# CropSenseMovement.net
KiCad netlist of a schematic drawn in Altium Designer
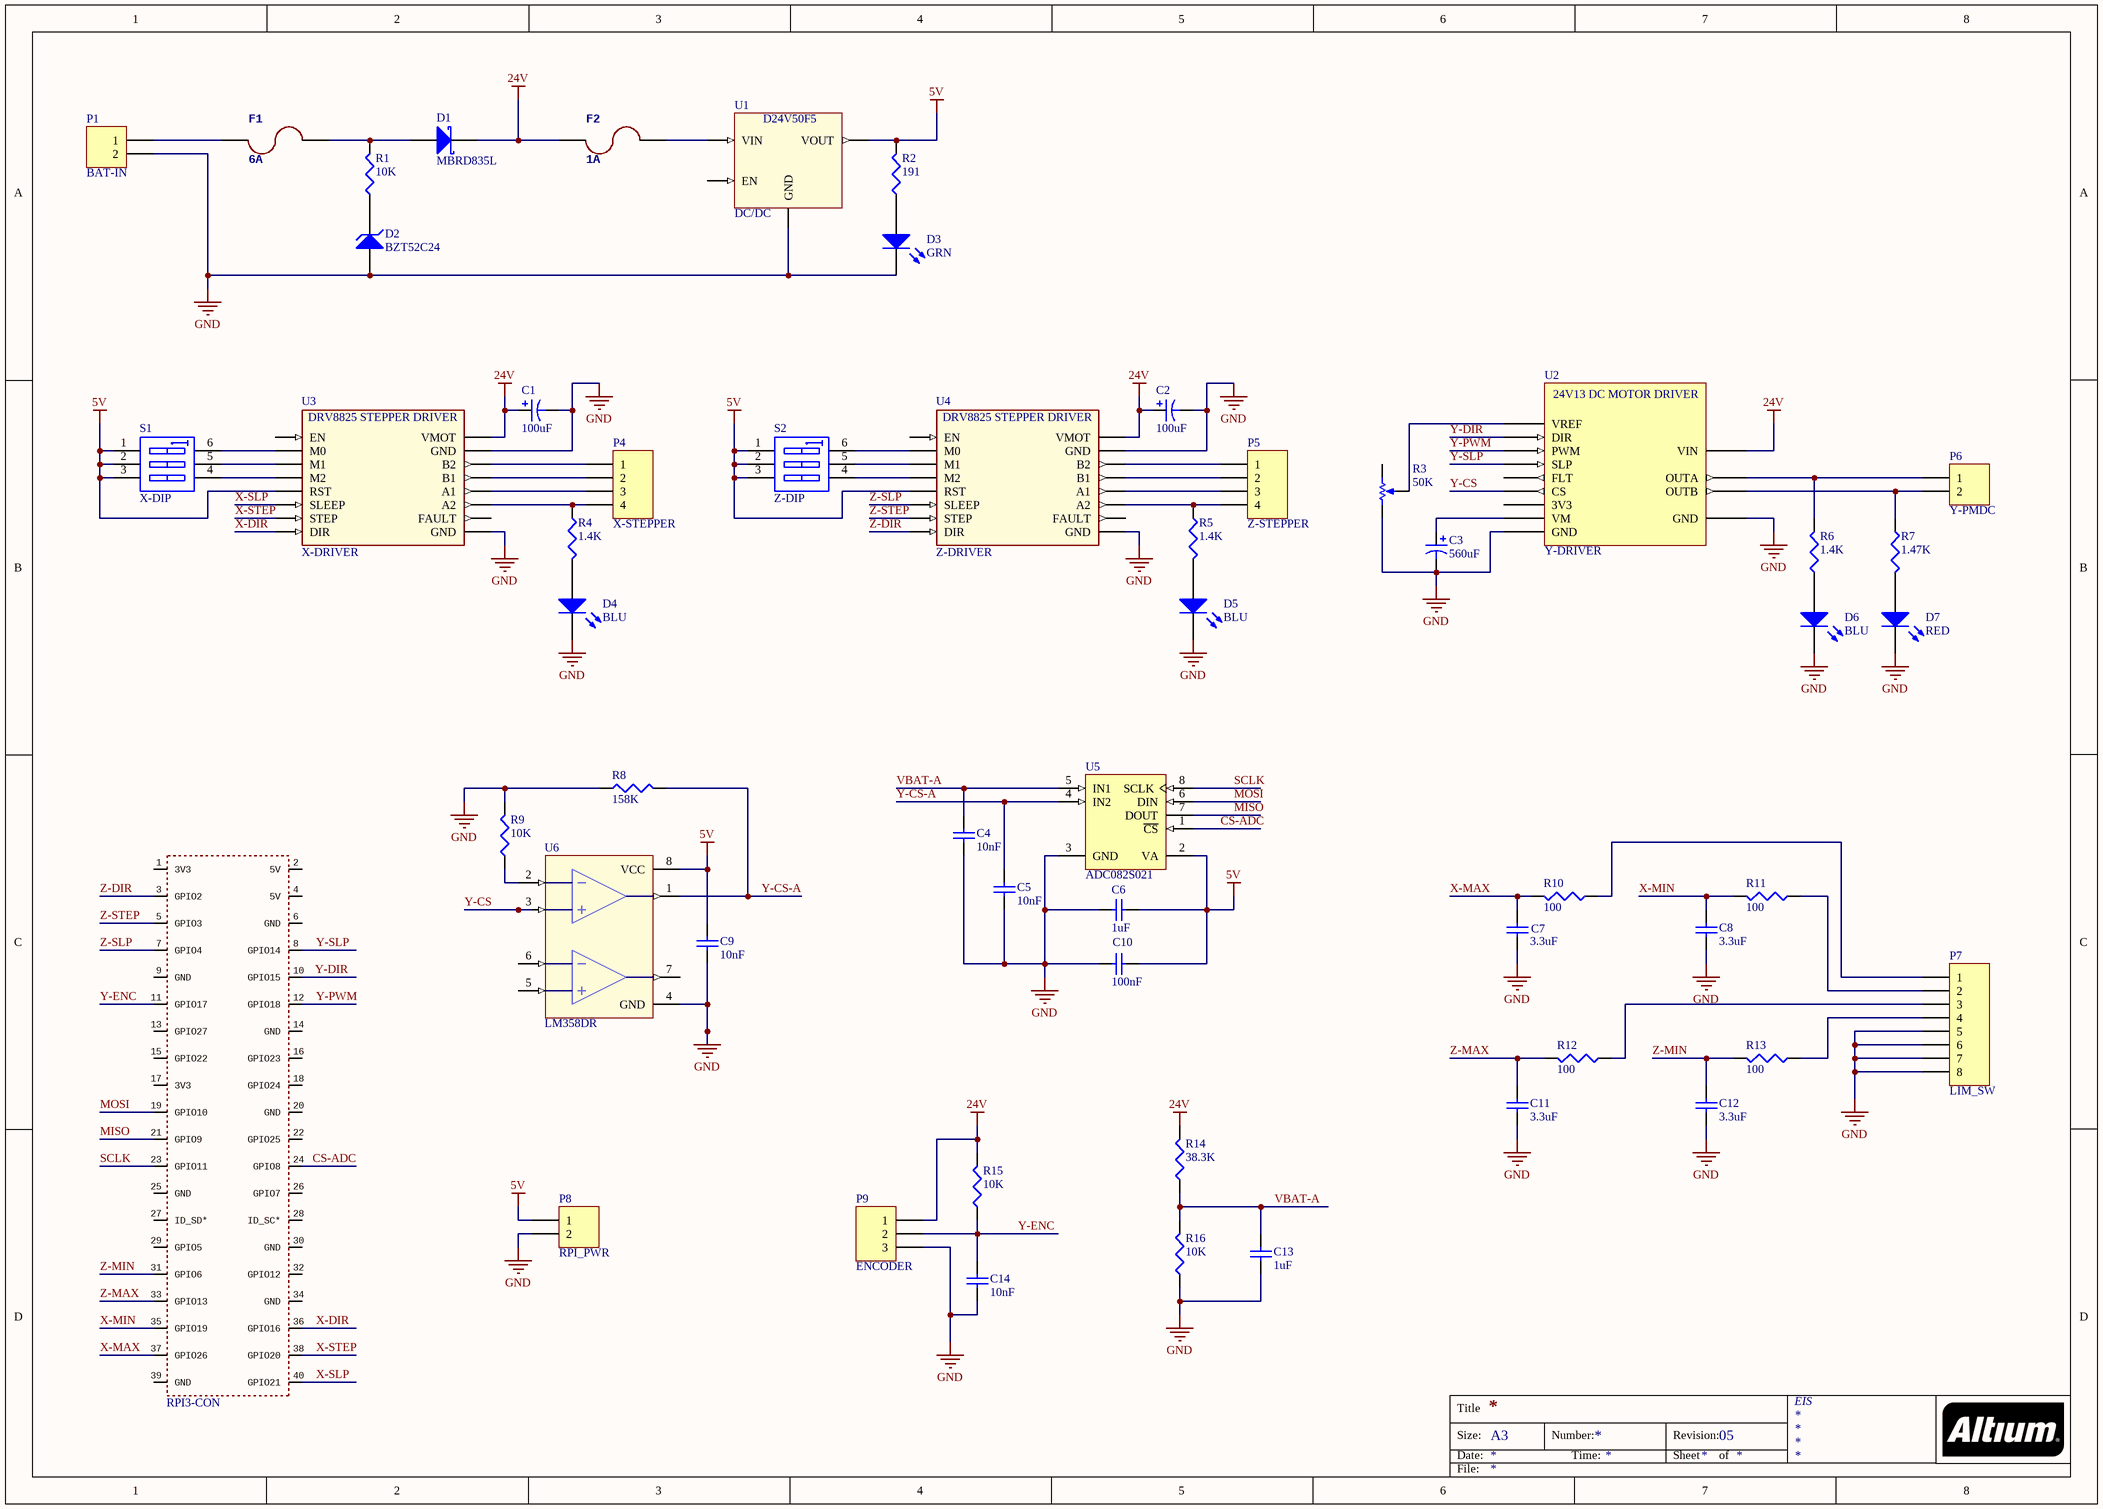
[diagram p0: CropSenseMovement.SchDoc]

(export (version "E")
  (design (tool "Eeschema 10.0.6"))
  (components
    (comp (ref "C1")
      (value "100uF")
      (footprint "CAP 8mm")
      (description "Polarized Capacitor (Axial)")
      (fields (field (name "PUBLISHER") "Altium Limited"))
      (libsource (lib "CropSense_Library") (part "Cap Pol"))
    )
    (comp (ref "C2")
      (value "100uF")
      (footprint "CAP 8mm")
      (description "Polarized Capacitor (Axial)")
      (fields (field (name "PUBLISHER") "Altium Limited"))
      (libsource (lib "CropSense_Library") (part "Cap Pol"))
    )
    (comp (ref "C3")
      (value "560uF")
      (footprint "CAP 12.5MM")
      (description "Polarized Capacitor (Axial)")
      (fields (field (name "PUBLISHER") "Altium Limited"))
      (libsource (lib "CropSense_Library") (part "Cap Pol"))
    )
    (comp (ref "C4")
      (value "10nF")
      (footprint "C1206")
      (description "Capacitor (Semiconductor SIM Model)")
      (fields (field (name "PUBLISHER") "Altium Limited"))
      (libsource (lib "Miscellaneous Devices") (part "Cap Semi"))
    )
    (comp (ref "C5")
      (value "10nF")
      (footprint "C1206")
      (description "Capacitor (Semiconductor SIM Model)")
      (fields (field (name "PUBLISHER") "Altium Limited"))
      (libsource (lib "Miscellaneous Devices") (part "Cap Semi"))
    )
    (comp (ref "C6")
      (value "1uF")
      (footprint "C1206")
      (description "Capacitor (Semiconductor SIM Model)")
      (fields (field (name "PUBLISHER") "Altium Limited"))
      (libsource (lib "Miscellaneous Devices") (part "Cap Semi"))
    )
    (comp (ref "C7")
      (value "3.3uF")
      (footprint "C1206")
      (description "Capacitor (Semiconductor SIM Model)")
      (fields (field (name "PUBLISHER") "Altium Limited"))
      (libsource (lib "Miscellaneous Devices") (part "Cap Semi"))
    )
    (comp (ref "C8")
      (value "3.3uF")
      (footprint "C1206")
      (description "Capacitor (Semiconductor SIM Model)")
      (fields (field (name "PUBLISHER") "Altium Limited"))
      (libsource (lib "Miscellaneous Devices") (part "Cap Semi"))
    )
    (comp (ref "C9")
      (value "10nF")
      (footprint "C1206")
      (description "Capacitor (Semiconductor SIM Model)")
      (fields (field (name "PUBLISHER") "Altium Limited"))
      (libsource (lib "Miscellaneous Devices") (part "Cap Semi"))
    )
    (comp (ref "C10")
      (value "100nF")
      (footprint "C1206")
      (description "Capacitor (Semiconductor SIM Model)")
      (fields (field (name "PUBLISHER") "Altium Limited"))
      (libsource (lib "Miscellaneous Devices") (part "Cap Semi"))
    )
    (comp (ref "C11")
      (value "3.3uF")
      (footprint "C1206")
      (description "Capacitor (Semiconductor SIM Model)")
      (fields (field (name "PUBLISHER") "Altium Limited"))
      (libsource (lib "Miscellaneous Devices") (part "Cap Semi"))
    )
    (comp (ref "C12")
      (value "3.3uF")
      (footprint "C1206")
      (description "Capacitor (Semiconductor SIM Model)")
      (fields (field (name "PUBLISHER") "Altium Limited"))
      (libsource (lib "Miscellaneous Devices") (part "Cap Semi"))
    )
    (comp (ref "C13")
      (value "1uF")
      (footprint "C1206")
      (description "Capacitor (Semiconductor SIM Model)")
      (fields (field (name "PUBLISHER") "Altium Limited"))
      (libsource (lib "Miscellaneous Devices") (part "Cap Semi"))
    )
    (comp (ref "C14")
      (value "10nF")
      (footprint "C1206")
      (description "Capacitor (Semiconductor SIM Model)")
      (fields (field (name "PUBLISHER") "Altium Limited"))
      (libsource (lib "Miscellaneous Devices") (part "Cap Semi"))
    )
    (comp (ref "D1")
      (value "MBRD835L")
      (footprint "DPAK229P991X238-3N")
      (description "Schottky Diode")
      (fields (field (name "PUBLISHER") "Altium Limited"))
      (libsource (lib "CropSense_Library") (part "D Schottky"))
    )
    (comp (ref "D2")
      (value "BZT52C24")
      (footprint "SOD123")
      (description "Zener Diode")
      (fields (field (name "PUBLISHER") "Altium Limited"))
      (libsource (lib "CropSense_Library") (part "D Zener"))
    )
    (comp (ref "D3")
      (value "GRN")
      (footprint "1206 SMD LED")
      (description "Typical INFRARED GaAs LED")
      (fields (field (name "PUBLISHER") "Altium Limited"))
      (libsource (lib "CropSense_Library") (part "LED"))
    )
    (comp (ref "D4")
      (value "BLU")
      (footprint "1206 SMD LED")
      (description "Typical INFRARED GaAs LED")
      (fields (field (name "PUBLISHER") "Altium Limited"))
      (libsource (lib "CropSense_Library") (part "LED"))
    )
    (comp (ref "D5")
      (value "BLU")
      (footprint "1206 SMD LED")
      (description "Typical INFRARED GaAs LED")
      (fields (field (name "PUBLISHER") "Altium Limited"))
      (libsource (lib "CropSense_Library") (part "LED"))
    )
    (comp (ref "D6")
      (value "BLU")
      (footprint "1206 SMD LED")
      (description "Typical INFRARED GaAs LED")
      (fields (field (name "PUBLISHER") "Altium Limited"))
      (libsource (lib "CropSense_Library") (part "LED"))
    )
    (comp (ref "D7")
      (value "RED")
      (footprint "1206 SMD LED")
      (description "Typical INFRARED GaAs LED")
      (fields (field (name "PUBLISHER") "Altium Limited"))
      (libsource (lib "CropSense_Library") (part "LED"))
    )
    (comp (ref "F1")
      (value "6A")
      (footprint "5X20MM_LITTLEFUSE_CARTRIDGE")
      (description "5mm x 20mm Littlefuse Cartridge")
      (libsource (lib "CropSense_Library") (part "FUSE_5X20_LITTLEFUSE"))
    )
    (comp (ref "F2")
      (value "1A")
      (footprint "5X20MM_LITTLEFUSE_CARTRIDGE")
      (description "5mm x 20mm Littlefuse Cartridge")
      (libsource (lib "CropSense_Library") (part "FUSE_5X20_LITTLEFUSE"))
    )
    (comp (ref "P1")
      (value "BAT-IN")
      (footprint "MOLEX_MINI_1X2CCT")
      (description "Molex Mini Fit 2 cct Double Row")
      (libsource (lib "") (part "MOLEX_MINI_1X2_1"))
    )
    (comp (ref "P4")
      (value "X-STEPPER")
      (footprint "MOLEX_Micro_4x1CCT")
      (description "MOLEX_MICRO_4x1")
      (libsource (lib "CropSense_Library") (part "MOLEX_MICRO_4x1"))
    )
    (comp (ref "P5")
      (value "Z-STEPPER")
      (footprint "MOLEX_Micro_4x1CCT")
      (description "MOLEX_MICRO_4x1")
      (libsource (lib "CropSense_Library") (part "MOLEX_MICRO_4x1"))
    )
    (comp (ref "P6")
      (value "Y-PMDC")
      (footprint "MOLEX_MINI_1X2CCT")
      (description "Molex Mini Fit 2 cct Double Row")
      (libsource (lib "CropSense_Library") (part "MOLEX_MINI_1X2"))
    )
    (comp (ref "P7")
      (value "LIM_SW")
      (footprint "MOLEX_MICRO_4X2CCT")
      (description "Molex Micro Fit 8 cct Double Row")
      (libsource (lib "CropSense_Library") (part "MOLEX_MICRO_4X2"))
    )
    (comp (ref "P8")
      (value "RPI_PWR")
      (footprint "MOLEX_MICRO_2X1CCT")
      (description "Molex Micro Fit 2 cct Single Row")
      (libsource (lib "CropSense_Library") (part "MOLEX_MICRO_2x1"))
    )
    (comp (ref "P9")
      (value "ENCODER")
      (footprint "MOLEX_MICRO_3X1CCT")
      (description "Molex Micro Fit 3 cct Single Row")
      (libsource (lib "CropSense_Library") (part "MOLEX_MICRO_3x1"))
    )
    (comp (ref "R1")
      (value "10K")
      (footprint "6-0805_N")
      (description "Resistor")
      (fields (field (name "PUBLISHER") "Altium Limited"))
      (libsource (lib "Miscellaneous Devices") (part "Res3"))
    )
    (comp (ref "R2")
      (value "191")
      (footprint "6-0805_N")
      (description "Resistor")
      (fields (field (name "PUBLISHER") "Altium Limited"))
      (libsource (lib "Miscellaneous Devices") (part "Res3"))
    )
    (comp (ref "R3")
      (value "50K")
      (footprint "Trimpot TC33")
      (description "TRIMMER 50K OHM 0.1W SMD")
      (fields (field (name "PUBLISHER") "Altium Limited"))
      (libsource (lib "CropSense_Library") (part "RPot"))
    )
    (comp (ref "R4")
      (value "1.4K")
      (footprint "6-0805_N")
      (description "Resistor")
      (fields (field (name "PUBLISHER") "Altium Limited"))
      (libsource (lib "Miscellaneous Devices") (part "Res3"))
    )
    (comp (ref "R5")
      (value "1.4K")
      (footprint "6-0805_N")
      (description "Resistor")
      (fields (field (name "PUBLISHER") "Altium Limited"))
      (libsource (lib "Miscellaneous Devices") (part "Res3"))
    )
    (comp (ref "R6")
      (value "1.4K")
      (footprint "6-0805_N")
      (description "Resistor")
      (fields (field (name "PUBLISHER") "Altium Limited"))
      (libsource (lib "Miscellaneous Devices") (part "Res3"))
    )
    (comp (ref "R7")
      (value "1.47K")
      (footprint "6-0805_N")
      (description "Resistor")
      (fields (field (name "PUBLISHER") "Altium Limited"))
      (libsource (lib "Miscellaneous Devices") (part "Res3"))
    )
    (comp (ref "R8")
      (value "158K")
      (footprint "6-0805_N")
      (description "Resistor")
      (fields (field (name "PUBLISHER") "Altium Limited"))
      (libsource (lib "Miscellaneous Devices") (part "Res3"))
    )
    (comp (ref "R9")
      (value "10K")
      (footprint "6-0805_N")
      (description "Resistor")
      (fields (field (name "PUBLISHER") "Altium Limited"))
      (libsource (lib "Miscellaneous Devices") (part "Res3"))
    )
    (comp (ref "R10")
      (value "100")
      (footprint "6-0805_N")
      (description "Resistor")
      (fields (field (name "PUBLISHER") "Altium Limited"))
      (libsource (lib "Miscellaneous Devices") (part "Res3"))
    )
    (comp (ref "R11")
      (value "100")
      (footprint "6-0805_N")
      (description "Resistor")
      (fields (field (name "PUBLISHER") "Altium Limited"))
      (libsource (lib "Miscellaneous Devices") (part "Res3"))
    )
    (comp (ref "R12")
      (value "100")
      (footprint "6-0805_N")
      (description "Resistor")
      (fields (field (name "PUBLISHER") "Altium Limited"))
      (libsource (lib "Miscellaneous Devices") (part "Res3"))
    )
    (comp (ref "R13")
      (value "100")
      (footprint "6-0805_N")
      (description "Resistor")
      (fields (field (name "PUBLISHER") "Altium Limited"))
      (libsource (lib "Miscellaneous Devices") (part "Res3"))
    )
    (comp (ref "R14")
      (value "38.3K")
      (footprint "6-0805_N")
      (description "Resistor")
      (fields (field (name "PUBLISHER") "Altium Limited"))
      (libsource (lib "Miscellaneous Devices") (part "Res3"))
    )
    (comp (ref "R15")
      (value "10K")
      (footprint "6-0805_N")
      (description "Resistor")
      (fields (field (name "PUBLISHER") "Altium Limited"))
      (libsource (lib "Miscellaneous Devices") (part "Res3"))
    )
    (comp (ref "R16")
      (value "10K")
      (footprint "6-0805_N")
      (description "Resistor")
      (fields (field (name "PUBLISHER") "Altium Limited"))
      (libsource (lib "Miscellaneous Devices") (part "Res3"))
    )
    (comp (ref "S1")
      (value "X-DIP")
      (footprint "DIP-6")
      (description "DIP Switch, 3 Position, SPST")
      (fields (field (name "PUBLISHER") "Altium Limited"))
      (libsource (lib "Miscellaneous Devices") (part "SW DIP-3"))
    )
    (comp (ref "S2")
      (value "Z-DIP")
      (footprint "DIP-6")
      (description "DIP Switch, 3 Position, SPST")
      (fields (field (name "PUBLISHER") "Altium Limited"))
      (libsource (lib "Miscellaneous Devices") (part "SW DIP-3"))
    )
    (comp (ref "U$2")
      (value "RPI3-CON")
      (footprint "CONNECTOR")
      (libsource (lib "e14_Rpi3_RevA") (part "RPI3_CON"))
    )
    (comp (ref "U1")
      (value "DC/DC")
      (footprint "D24VXXFX_BREAKOUT")
      (libsource (lib "CropSense_Library") (part "D24V50F5"))
    )
    (comp (ref "U2")
      (value "Y-DRIVER")
      (footprint "24V13_BREAKOUT")
      (libsource (lib "CropSense_Library") (part "24V13_BREAKOUT"))
    )
    (comp (ref "U3")
      (value "X-DRIVER")
      (footprint "DRV8825_BREAKOUT")
      (libsource (lib "CropSense_Library") (part "DRV8825_BREAKOUT"))
    )
    (comp (ref "U4")
      (value "Z-DRIVER")
      (footprint "DRV8825_BREAKOUT")
      (libsource (lib "CropSense_Library") (part "DRV8825_BREAKOUT"))
    )
    (comp (ref "U5")
      (value "ADC082S021")
      (footprint "TI-DGK8_N")
      (description "2 Channel, 50 to 200 kSPS 8-Bit ADC, -40 to 85 degC, 8-pin SOP (DGK8), Green (RoHS & no Sb/Br)")
      (fields
        (field (name "PARTNUMBER") "ADC122S051QIMM/NOPB")
        (field (name "MANUFACTURER") "Texas Instruments")
      )
      (libsource (lib "Altium Content Vault") (part "CMP-0003-00004-1"))
    )
    (comp (ref "U6")
      (value "LM358DR")
      (footprint "SOIC127P600X175-8N")
      (libsource (lib "CropSense_Library") (part "LM358DR"))
    )
  )
  (nets
    (net (code "1") (name "/CS-ADC") (class "Default")
      (node (ref "U$2") (pin "24") (pinfunction "GPIO8_24") (pintype "passive"))
      (node (ref "U5") (pin "1") (pinfunction "~{CS}_1") (pintype "input"))
    )
    (net (code "2") (name "/MISO") (class "Default")
      (node (ref "U$2") (pin "21") (pinfunction "GPIO9_21") (pintype "passive"))
      (node (ref "U5") (pin "7") (pinfunction "DOUT_7") (pintype "tri_state"))
    )
    (net (code "3") (name "/MOSI") (class "Default")
      (node (ref "U$2") (pin "19") (pinfunction "GPIO10_19") (pintype "passive"))
      (node (ref "U5") (pin "6") (pinfunction "DIN_6") (pintype "input"))
    )
    (net (code "4") (name "/SCLK") (class "Default")
      (node (ref "U$2") (pin "23") (pinfunction "GPIO11_23") (pintype "passive"))
      (node (ref "U5") (pin "8") (pinfunction "SCLK_8") (pintype "input"))
    )
    (net (code "5") (name "/VBAT-A") (class "Default")
      (node (ref "C13") (pin "2") (pinfunction "2_2") (pintype "passive"))
      (node (ref "C4") (pin "1") (pinfunction "1_1") (pintype "passive"))
      (node (ref "R14") (pin "1") (pinfunction "1_1") (pintype "passive"))
      (node (ref "R16") (pin "2") (pinfunction "2_2") (pintype "passive"))
      (node (ref "U5") (pin "5") (pinfunction "IN1_5") (pintype "input"))
    )
    (net (code "6") (name "/X-DIR") (class "Default")
      (node (ref "U$2") (pin "36") (pinfunction "GPIO16_36") (pintype "passive"))
      (node (ref "U3") (pin "DIR") (pinfunction "DIR_DIR") (pintype "input"))
    )
    (net (code "7") (name "/X-MAX") (class "Default")
      (node (ref "C7") (pin "2") (pinfunction "2_2") (pintype "passive"))
      (node (ref "R10") (pin "2") (pinfunction "2_2") (pintype "passive"))
      (node (ref "U$2") (pin "37") (pinfunction "GPIO26_37") (pintype "passive"))
    )
    (net (code "8") (name "/X-MIN") (class "Default")
      (node (ref "C8") (pin "2") (pinfunction "2_2") (pintype "passive"))
      (node (ref "R11") (pin "2") (pinfunction "2_2") (pintype "passive"))
      (node (ref "U$2") (pin "35") (pinfunction "GPIO19_35") (pintype "passive"))
    )
    (net (code "9") (name "/X-SLP") (class "Default")
      (node (ref "U$2") (pin "40") (pinfunction "GPIO21_40") (pintype "passive"))
      (node (ref "U3") (pin "SLP") (pinfunction "SLEEP_SLP") (pintype "input"))
    )
    (net (code "10") (name "/X-STEP") (class "Default")
      (node (ref "U$2") (pin "38") (pinfunction "GPIO20_38") (pintype "passive"))
      (node (ref "U3") (pin "STEP") (pinfunction "STEP_STEP") (pintype "input"))
    )
    (net (code "11") (name "/Y-CS") (class "Default")
      (node (ref "U2") (pin "CS") (pinfunction "CS_CS") (pintype "output"))
      (node (ref "U6") (pin "3") (pinfunction "IN1+_3") (pintype "input"))
    )
    (net (code "12") (name "/Y-CS-A") (class "Default")
      (node (ref "C5") (pin "1") (pinfunction "1_1") (pintype "passive"))
      (node (ref "R8") (pin "2") (pinfunction "2_2") (pintype "passive"))
      (node (ref "U5") (pin "4") (pinfunction "IN2_4") (pintype "input"))
      (node (ref "U6") (pin "1") (pinfunction "OUT1_1") (pintype "output"))
    )
    (net (code "13") (name "/Y-DIR") (class "Default")
      (node (ref "U$2") (pin "10") (pinfunction "GPIO15_10") (pintype "passive"))
      (node (ref "U2") (pin "DIR") (pinfunction "DIR_DIR") (pintype "input"))
    )
    (net (code "14") (name "/Y-ENC") (class "Default")
      (node (ref "C14") (pin "2") (pinfunction "2_2") (pintype "passive"))
      (node (ref "P9") (pin "2") (pinfunction "2_2") (pintype "passive"))
      (node (ref "R15") (pin "1") (pinfunction "1_1") (pintype "passive"))
      (node (ref "U$2") (pin "11") (pinfunction "GPIO17_11") (pintype "passive"))
    )
    (net (code "15") (name "/Y-PWM") (class "Default")
      (node (ref "U$2") (pin "12") (pinfunction "GPIO18_12") (pintype "passive"))
      (node (ref "U2") (pin "PWM") (pinfunction "PWM_PWM") (pintype "input"))
    )
    (net (code "16") (name "/Y-SLP") (class "Default")
      (node (ref "U$2") (pin "8") (pinfunction "GPIO14_8") (pintype "passive"))
      (node (ref "U2") (pin "SLP") (pinfunction "SLP_SLP") (pintype "input"))
    )
    (net (code "17") (name "/Z-DIR") (class "Default")
      (node (ref "U$2") (pin "3") (pinfunction "GPIO2_3") (pintype "passive"))
      (node (ref "U4") (pin "DIR") (pinfunction "DIR_DIR") (pintype "input"))
    )
    (net (code "18") (name "/Z-MAX") (class "Default")
      (node (ref "C11") (pin "2") (pinfunction "2_2") (pintype "passive"))
      (node (ref "R12") (pin "2") (pinfunction "2_2") (pintype "passive"))
      (node (ref "U$2") (pin "33") (pinfunction "GPIO13_33") (pintype "passive"))
    )
    (net (code "19") (name "/Z-MIN") (class "Default")
      (node (ref "C12") (pin "2") (pinfunction "2_2") (pintype "passive"))
      (node (ref "R13") (pin "2") (pinfunction "2_2") (pintype "passive"))
      (node (ref "U$2") (pin "31") (pinfunction "GPIO6_31") (pintype "passive"))
    )
    (net (code "20") (name "/Z-SLP") (class "Default")
      (node (ref "U$2") (pin "7") (pinfunction "GPIO4_7") (pintype "passive"))
      (node (ref "U4") (pin "SLP") (pinfunction "SLEEP_SLP") (pintype "input"))
    )
    (net (code "21") (name "/Z-STEP") (class "Default")
      (node (ref "U$2") (pin "5") (pinfunction "GPIO3_5") (pintype "passive"))
      (node (ref "U4") (pin "STEP") (pinfunction "STEP_STEP") (pintype "input"))
    )
    (net (code "22") (name "5V") (class "Default")
      (node (ref "C10") (pin "2") (pinfunction "2_2") (pintype "passive"))
      (node (ref "C6") (pin "2") (pinfunction "2_2") (pintype "passive"))
      (node (ref "C9") (pin "1") (pinfunction "1_1") (pintype "passive"))
      (node (ref "P8") (pin "1") (pinfunction "1_1") (pintype "passive"))
      (node (ref "R2") (pin "2") (pinfunction "2_2") (pintype "passive"))
      (node (ref "S1") (pin "1") (pinfunction "A1_1") (pintype "passive"))
      (node (ref "S1") (pin "2") (pinfunction "A2_2") (pintype "passive"))
      (node (ref "S1") (pin "3") (pinfunction "A3_3") (pintype "passive"))
      (node (ref "S2") (pin "1") (pinfunction "A1_1") (pintype "passive"))
      (node (ref "S2") (pin "2") (pinfunction "A2_2") (pintype "passive"))
      (node (ref "S2") (pin "3") (pinfunction "A3_3") (pintype "passive"))
      (node (ref "U1") (pin "VOUT") (pinfunction "VOUT_VOUT") (pintype "output"))
      (node (ref "U3") (pin "RST") (pinfunction "RST_RST") (pintype "passive"))
      (node (ref "U4") (pin "RST") (pinfunction "RST_RST") (pintype "passive"))
      (node (ref "U5") (pin "2") (pinfunction "VA_2") (pintype "power_in"))
      (node (ref "U6") (pin "8") (pinfunction "VCC_8") (pintype "power_in"))
    )
    (net (code "23") (name "24V") (class "Default")
      (node (ref "C1") (pin "1") (pinfunction "1_1") (pintype "passive"))
      (node (ref "C2") (pin "1") (pinfunction "1_1") (pintype "passive"))
      (node (ref "D1") (pin "2") (pinfunction "K_2") (pintype "passive"))
      (node (ref "F2") (pin "1") (pinfunction "1_1") (pintype "passive"))
      (node (ref "P9") (pin "1") (pinfunction "1_1") (pintype "passive"))
      (node (ref "R14") (pin "2") (pinfunction "2_2") (pintype "passive"))
      (node (ref "R15") (pin "2") (pinfunction "2_2") (pintype "passive"))
      (node (ref "U2") (pin "VIN") (pinfunction "VIN_VIN") (pintype "power_in"))
      (node (ref "U3") (pin "VMOT") (pinfunction "VMOT_VMOT") (pintype "power_in"))
      (node (ref "U4") (pin "VMOT") (pinfunction "VMOT_VMOT") (pintype "power_in"))
    )
    (net (code "24") (name "GND") (class "Default")
      (node (ref "C1") (pin "2") (pinfunction "2_2") (pintype "passive"))
      (node (ref "C10") (pin "1") (pinfunction "1_1") (pintype "passive"))
      (node (ref "C11") (pin "1") (pinfunction "1_1") (pintype "passive"))
      (node (ref "C12") (pin "1") (pinfunction "1_1") (pintype "passive"))
      (node (ref "C13") (pin "1") (pinfunction "1_1") (pintype "passive"))
      (node (ref "C14") (pin "1") (pinfunction "1_1") (pintype "passive"))
      (node (ref "C2") (pin "2") (pinfunction "2_2") (pintype "passive"))
      (node (ref "C3") (pin "2") (pinfunction "2_2") (pintype "passive"))
      (node (ref "C4") (pin "2") (pinfunction "2_2") (pintype "passive"))
      (node (ref "C5") (pin "2") (pinfunction "2_2") (pintype "passive"))
      (node (ref "C6") (pin "1") (pinfunction "1_1") (pintype "passive"))
      (node (ref "C7") (pin "1") (pinfunction "1_1") (pintype "passive"))
      (node (ref "C8") (pin "1") (pinfunction "1_1") (pintype "passive"))
      (node (ref "C9") (pin "2") (pinfunction "2_2") (pintype "passive"))
      (node (ref "D2") (pin "1") (pinfunction "A_1") (pintype "passive"))
      (node (ref "D3") (pin "2") (pinfunction "K_2") (pintype "passive"))
      (node (ref "D4") (pin "2") (pinfunction "K_2") (pintype "passive"))
      (node (ref "D5") (pin "2") (pinfunction "K_2") (pintype "passive"))
      (node (ref "D6") (pin "2") (pinfunction "K_2") (pintype "passive"))
      (node (ref "D7") (pin "2") (pinfunction "K_2") (pintype "passive"))
      (node (ref "P1") (pin "2") (pinfunction "2_2") (pintype "passive"))
      (node (ref "P7") (pin "5") (pinfunction "5_5") (pintype "passive"))
      (node (ref "P7") (pin "6") (pinfunction "6_6") (pintype "passive"))
      (node (ref "P7") (pin "7") (pinfunction "7_7") (pintype "passive"))
      (node (ref "P7") (pin "8") (pinfunction "8_8") (pintype "passive"))
      (node (ref "P8") (pin "2") (pinfunction "2_2") (pintype "passive"))
      (node (ref "P9") (pin "3") (pinfunction "3_3") (pintype "passive"))
      (node (ref "R16") (pin "1") (pinfunction "1_1") (pintype "passive"))
      (node (ref "R3") (pin "3") (pinfunction "TOP_3") (pintype "passive"))
      (node (ref "R8") (pin "1") (pinfunction "1_1") (pintype "passive"))
      (node (ref "R9") (pin "2") (pinfunction "2_2") (pintype "passive"))
      (node (ref "U1") (pin "GND") (pinfunction "GND_GND") (pintype "passive"))
      (node (ref "U2") (pin "GND") (pinfunction "GND_GND") (pintype "passive"))
      (node (ref "U3") (pin "GND") (pinfunction "GND_GND") (pintype "power_in"))
      (node (ref "U4") (pin "GND") (pinfunction "GND_GND") (pintype "power_in"))
      (node (ref "U5") (pin "3") (pinfunction "GND_3") (pintype "power_in"))
      (node (ref "U6") (pin "4") (pinfunction "GND_4") (pintype "power_in"))
    )
    (net (code "25") (name "Net-(C3-Pad1)") (class "Default")
      (node (ref "C3") (pin "1") (pinfunction "1_1") (pintype "passive"))
      (node (ref "U2") (pin "VM") (pinfunction "VM_VM") (pintype "passive"))
    )
    (net (code "26") (name "Net-(D1-A)") (class "Default")
      (node (ref "D1") (pin "1") (pinfunction "A_1") (pintype "passive"))
      (node (ref "F1") (pin "2") (pinfunction "2_2") (pintype "passive"))
      (node (ref "R1") (pin "2") (pinfunction "2_2") (pintype "passive"))
    )
    (net (code "27") (name "Net-(D2-K)") (class "Default")
      (node (ref "D2") (pin "2") (pinfunction "K_2") (pintype "passive"))
      (node (ref "R1") (pin "1") (pinfunction "1_1") (pintype "passive"))
    )
    (net (code "28") (name "Net-(D3-A)") (class "Default")
      (node (ref "D3") (pin "1") (pinfunction "A_1") (pintype "passive"))
      (node (ref "R2") (pin "1") (pinfunction "1_1") (pintype "passive"))
    )
    (net (code "29") (name "Net-(D4-A)") (class "Default")
      (node (ref "D4") (pin "1") (pinfunction "A_1") (pintype "passive"))
      (node (ref "R4") (pin "2") (pinfunction "2_2") (pintype "passive"))
    )
    (net (code "30") (name "Net-(D5-A)") (class "Default")
      (node (ref "D5") (pin "1") (pinfunction "A_1") (pintype "passive"))
      (node (ref "R5") (pin "2") (pinfunction "2_2") (pintype "passive"))
    )
    (net (code "31") (name "Net-(D6-A)") (class "Default")
      (node (ref "D6") (pin "1") (pinfunction "A_1") (pintype "passive"))
      (node (ref "R6") (pin "1") (pinfunction "1_1") (pintype "passive"))
    )
    (net (code "32") (name "Net-(D7-A)") (class "Default")
      (node (ref "D7") (pin "1") (pinfunction "A_1") (pintype "passive"))
      (node (ref "R7") (pin "2") (pinfunction "2_2") (pintype "passive"))
    )
    (net (code "33") (name "Net-(F1-Pad1)") (class "Default")
      (node (ref "F1") (pin "1") (pinfunction "1_1") (pintype "passive"))
      (node (ref "P1") (pin "1") (pinfunction "1_1") (pintype "passive"))
    )
    (net (code "34") (name "Net-(F2-Pad2)") (class "Default")
      (node (ref "F2") (pin "2") (pinfunction "2_2") (pintype "passive"))
      (node (ref "U1") (pin "VIN") (pinfunction "VIN_VIN") (pintype "input"))
    )
    (net (code "35") (name "Net-(P4-Pad1)") (class "Default")
      (node (ref "P4") (pin "1") (pinfunction "1_1") (pintype "passive"))
      (node (ref "U3") (pin "B2") (pinfunction "B2_B2") (pintype "output"))
    )
    (net (code "36") (name "Net-(P4-Pad2)") (class "Default")
      (node (ref "P4") (pin "2") (pinfunction "2_2") (pintype "passive"))
      (node (ref "U3") (pin "B1") (pinfunction "B1_B1") (pintype "output"))
    )
    (net (code "37") (name "Net-(P4-Pad3)") (class "Default")
      (node (ref "P4") (pin "3") (pinfunction "3_3") (pintype "passive"))
      (node (ref "U3") (pin "A1") (pinfunction "A1_A1") (pintype "output"))
    )
    (net (code "38") (name "Net-(P4-Pad4)") (class "Default")
      (node (ref "P4") (pin "4") (pinfunction "4_4") (pintype "passive"))
      (node (ref "R4") (pin "1") (pinfunction "1_1") (pintype "passive"))
      (node (ref "U3") (pin "A2") (pinfunction "A2_A2") (pintype "output"))
    )
    (net (code "39") (name "Net-(P5-Pad1)") (class "Default")
      (node (ref "P5") (pin "1") (pinfunction "1_1") (pintype "passive"))
      (node (ref "U4") (pin "B2") (pinfunction "B2_B2") (pintype "output"))
    )
    (net (code "40") (name "Net-(P5-Pad2)") (class "Default")
      (node (ref "P5") (pin "2") (pinfunction "2_2") (pintype "passive"))
      (node (ref "U4") (pin "B1") (pinfunction "B1_B1") (pintype "output"))
    )
    (net (code "41") (name "Net-(P5-Pad3)") (class "Default")
      (node (ref "P5") (pin "3") (pinfunction "3_3") (pintype "passive"))
      (node (ref "U4") (pin "A1") (pinfunction "A1_A1") (pintype "output"))
    )
    (net (code "42") (name "Net-(P5-Pad4)") (class "Default")
      (node (ref "P5") (pin "4") (pinfunction "4_4") (pintype "passive"))
      (node (ref "R5") (pin "1") (pinfunction "1_1") (pintype "passive"))
      (node (ref "U4") (pin "A2") (pinfunction "A2_A2") (pintype "output"))
    )
    (net (code "43") (name "Net-(P6-Pad1)") (class "Default")
      (node (ref "P6") (pin "1") (pinfunction "1_1") (pintype "passive"))
      (node (ref "R6") (pin "2") (pinfunction "2_2") (pintype "passive"))
      (node (ref "U2") (pin "OUTA") (pinfunction "OUTA_OUTA") (pintype "output"))
    )
    (net (code "44") (name "Net-(P6-Pad2)") (class "Default")
      (node (ref "P6") (pin "2") (pinfunction "2_2") (pintype "passive"))
      (node (ref "R7") (pin "1") (pinfunction "1_1") (pintype "passive"))
      (node (ref "U2") (pin "OUTB") (pinfunction "OUTB_OUTB") (pintype "output"))
    )
    (net (code "45") (name "Net-(P7-Pad1)") (class "Default")
      (node (ref "P7") (pin "1") (pinfunction "1_1") (pintype "passive"))
      (node (ref "R10") (pin "1") (pinfunction "1_1") (pintype "passive"))
    )
    (net (code "46") (name "Net-(P7-Pad2)") (class "Default")
      (node (ref "P7") (pin "2") (pinfunction "2_2") (pintype "passive"))
      (node (ref "R11") (pin "1") (pinfunction "1_1") (pintype "passive"))
    )
    (net (code "47") (name "Net-(P7-Pad3)") (class "Default")
      (node (ref "P7") (pin "3") (pinfunction "3_3") (pintype "passive"))
      (node (ref "R12") (pin "1") (pinfunction "1_1") (pintype "passive"))
    )
    (net (code "48") (name "Net-(P7-Pad4)") (class "Default")
      (node (ref "P7") (pin "4") (pinfunction "4_4") (pintype "passive"))
      (node (ref "R13") (pin "1") (pinfunction "1_1") (pintype "passive"))
    )
    (net (code "49") (name "Net-(R3-TAP)") (class "Default")
      (node (ref "R3") (pin "2") (pinfunction "TAP_2") (pintype "passive"))
      (node (ref "U2") (pin "VREF") (pinfunction "VREF_VREF") (pintype "passive"))
    )
    (net (code "50") (name "Net-(S1-B1)") (class "Default")
      (node (ref "S1") (pin "6") (pinfunction "B1_6") (pintype "passive"))
      (node (ref "U3") (pin "M0") (pinfunction "M0_M0") (pintype "passive"))
    )
    (net (code "51") (name "Net-(S1-B2)") (class "Default")
      (node (ref "S1") (pin "5") (pinfunction "B2_5") (pintype "passive"))
      (node (ref "U3") (pin "M1") (pinfunction "M1_M1") (pintype "passive"))
    )
    (net (code "52") (name "Net-(S1-B3)") (class "Default")
      (node (ref "S1") (pin "4") (pinfunction "B3_4") (pintype "passive"))
      (node (ref "U3") (pin "M2") (pinfunction "M2_M2") (pintype "passive"))
    )
    (net (code "53") (name "Net-(S2-B1)") (class "Default")
      (node (ref "S2") (pin "6") (pinfunction "B1_6") (pintype "passive"))
      (node (ref "U4") (pin "M0") (pinfunction "M0_M0") (pintype "passive"))
    )
    (net (code "54") (name "Net-(S2-B2)") (class "Default")
      (node (ref "S2") (pin "5") (pinfunction "B2_5") (pintype "passive"))
      (node (ref "U4") (pin "M1") (pinfunction "M1_M1") (pintype "passive"))
    )
    (net (code "55") (name "Net-(S2-B3)") (class "Default")
      (node (ref "S2") (pin "4") (pinfunction "B3_4") (pintype "passive"))
      (node (ref "U4") (pin "M2") (pinfunction "M2_M2") (pintype "passive"))
    )
    (net (code "56") (name "Net-(U6-IN1-)") (class "Default")
      (node (ref "R9") (pin "1") (pinfunction "1_1") (pintype "passive"))
      (node (ref "U6") (pin "2") (pinfunction "IN1-_2") (pintype "input"))
    )
    (net (code "57") (name "unconnected-(R3-BOT-Pad1)") (class "Default")
      (node (ref "R3") (pin "1") (pinfunction "BOT_1") (pintype "passive"))
    )
    (net (code "58") (name "unconnected-(U$2-3V3-Pad1)") (class "Default")
      (node (ref "U$2") (pin "1") (pinfunction "3V3_1") (pintype "passive"))
    )
    (net (code "59") (name "unconnected-(U$2-3V3-Pad17)") (class "Default")
      (node (ref "U$2") (pin "17") (pinfunction "3V3_17") (pintype "passive"))
    )
    (net (code "60") (name "unconnected-(U$2-5V-Pad2)") (class "Default")
      (node (ref "U$2") (pin "2") (pinfunction "5V_2") (pintype "passive"))
    )
    (net (code "61") (name "unconnected-(U$2-5V-Pad4)") (class "Default")
      (node (ref "U$2") (pin "4") (pinfunction "5V_4") (pintype "passive"))
    )
    (net (code "62") (name "unconnected-(U$2-GND-Pad6)") (class "Default")
      (node (ref "U$2") (pin "6") (pinfunction "GND_6") (pintype "passive"))
    )
    (net (code "63") (name "unconnected-(U$2-GND-Pad9)") (class "Default")
      (node (ref "U$2") (pin "9") (pinfunction "GND_9") (pintype "passive"))
    )
    (net (code "64") (name "unconnected-(U$2-GND-Pad14)") (class "Default")
      (node (ref "U$2") (pin "14") (pinfunction "GND_14") (pintype "passive"))
    )
    (net (code "65") (name "unconnected-(U$2-GND-Pad20)") (class "Default")
      (node (ref "U$2") (pin "20") (pinfunction "GND_20") (pintype "passive"))
    )
    (net (code "66") (name "unconnected-(U$2-GND-Pad25)") (class "Default")
      (node (ref "U$2") (pin "25") (pinfunction "GND_25") (pintype "passive"))
    )
    (net (code "67") (name "unconnected-(U$2-GND-Pad30)") (class "Default")
      (node (ref "U$2") (pin "30") (pinfunction "GND_30") (pintype "passive"))
    )
    (net (code "68") (name "unconnected-(U$2-GND-Pad34)") (class "Default")
      (node (ref "U$2") (pin "34") (pinfunction "GND_34") (pintype "passive"))
    )
    (net (code "69") (name "unconnected-(U$2-GND-Pad39)") (class "Default")
      (node (ref "U$2") (pin "39") (pinfunction "GND_39") (pintype "passive"))
    )
    (net (code "70") (name "unconnected-(U$2-GPIO5-Pad29)") (class "Default")
      (node (ref "U$2") (pin "29") (pinfunction "GPIO5_29") (pintype "passive"))
    )
    (net (code "71") (name "unconnected-(U$2-GPIO7-Pad26)") (class "Default")
      (node (ref "U$2") (pin "26") (pinfunction "GPIO7_26") (pintype "passive"))
    )
    (net (code "72") (name "unconnected-(U$2-GPIO12-Pad32)") (class "Default")
      (node (ref "U$2") (pin "32") (pinfunction "GPIO12_32") (pintype "passive"))
    )
    (net (code "73") (name "unconnected-(U$2-GPIO22-Pad15)") (class "Default")
      (node (ref "U$2") (pin "15") (pinfunction "GPIO22_15") (pintype "passive"))
    )
    (net (code "74") (name "unconnected-(U$2-GPIO23-Pad16)") (class "Default")
      (node (ref "U$2") (pin "16") (pinfunction "GPIO23_16") (pintype "passive"))
    )
    (net (code "75") (name "unconnected-(U$2-GPIO24-Pad18)") (class "Default")
      (node (ref "U$2") (pin "18") (pinfunction "GPIO24_18") (pintype "passive"))
    )
    (net (code "76") (name "unconnected-(U$2-GPIO25-Pad22)") (class "Default")
      (node (ref "U$2") (pin "22") (pinfunction "GPIO25_22") (pintype "passive"))
    )
    (net (code "77") (name "unconnected-(U$2-GPIO27-Pad13)") (class "Default")
      (node (ref "U$2") (pin "13") (pinfunction "GPIO27_13") (pintype "passive"))
    )
    (net (code "78") (name "unconnected-(U$2-ID_SC*-Pad28)") (class "Default")
      (node (ref "U$2") (pin "28") (pinfunction "ID_SC*_28") (pintype "passive"))
    )
    (net (code "79") (name "unconnected-(U$2-ID_SD*-Pad27)") (class "Default")
      (node (ref "U$2") (pin "27") (pinfunction "ID_SD*_27") (pintype "passive"))
    )
    (net (code "80") (name "unconnected-(U1-PadEN)") (class "Default")
      (node (ref "U1") (pin "EN") (pinfunction "EN_EN") (pintype "input"))
    )
    (net (code "81") (name "unconnected-(U2-Pad3V3)") (class "Default")
      (node (ref "U2") (pin "3V3") (pinfunction "3V3_3V3") (pintype "passive"))
    )
    (net (code "82") (name "unconnected-(U2-PadFLT)") (class "Default")
      (node (ref "U2") (pin "FLT") (pinfunction "FLT_FLT") (pintype "output"))
    )
    (net (code "83") (name "unconnected-(U3-PadEN)") (class "Default")
      (node (ref "U3") (pin "EN") (pinfunction "EN_EN") (pintype "input"))
    )
    (net (code "84") (name "unconnected-(U3-PadFAULT)") (class "Default")
      (node (ref "U3") (pin "FAULT") (pinfunction "FAULT_FAULT") (pintype "output"))
    )
    (net (code "85") (name "unconnected-(U4-PadEN)") (class "Default")
      (node (ref "U4") (pin "EN") (pinfunction "EN_EN") (pintype "input"))
    )
    (net (code "86") (name "unconnected-(U4-PadFAULT)") (class "Default")
      (node (ref "U4") (pin "FAULT") (pinfunction "FAULT_FAULT") (pintype "output"))
    )
    (net (code "87") (name "unconnected-(U6-IN2+-Pad5)") (class "Default")
      (node (ref "U6") (pin "5") (pinfunction "IN2+_5") (pintype "input"))
    )
    (net (code "88") (name "unconnected-(U6-IN2--Pad6)") (class "Default")
      (node (ref "U6") (pin "6") (pinfunction "IN2-_6") (pintype "input"))
    )
    (net (code "89") (name "unconnected-(U6-OUT2-Pad7)") (class "Default")
      (node (ref "U6") (pin "7") (pinfunction "OUT2_7") (pintype "output"))
    )
  )
)
